# BPW34.net
KiCad netlist of a schematic drawn in EAGLE
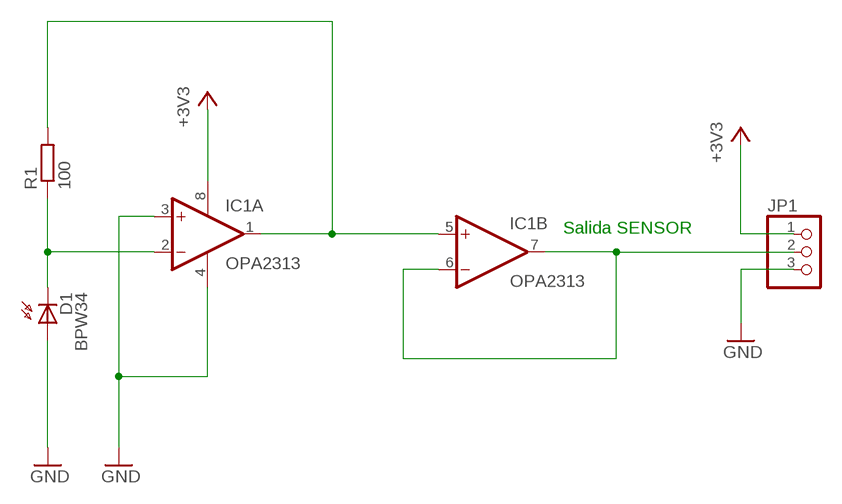
[diagram p0: schematic, sheet 1]

(export (version "E")
  (design (tool "Eeschema 10.0.6"))
  (components
    (comp (ref "D1")
      (value "BPW34")
      (footprint "eagle-import:BPW32")
      (libsource (lib "eagle-import") (part "BPW32"))
    )
    (comp (ref "IC1")
      (value "OPA2313")
      (footprint "eagle-import:SO08")
      (libsource (lib "eagle-import") (part "TL082D"))
    )
    (comp (ref "JP1")
      (value "PINHD-1X3")
      (footprint "eagle-import:1X03")
      (libsource (lib "eagle-import") (part "PINHD-1X3"))
    )
    (comp (ref "R1")
      (value "100")
      (footprint "eagle-import:0207_10")
      (libsource (lib "eagle-import") (part "R-EU_0207/10"))
    )
  )
  (nets
    (net (code "1") (name "+3V3") (class "Default")
      (node (ref "IC1") (pin "8") (pinfunction "V+_8") (pintype "power_in"))
      (node (ref "JP1") (pin "1") (pinfunction "1_1") (pintype "passive"))
    )
    (net (code "2") (name "GND") (class "Default")
      (node (ref "D1") (pin "A") (pinfunction "A_A") (pintype "passive"))
      (node (ref "IC1") (pin "3") (pinfunction "+IN_3") (pintype "input"))
      (node (ref "IC1") (pin "4") (pinfunction "V-_4") (pintype "power_in"))
      (node (ref "JP1") (pin "3") (pinfunction "3_3") (pintype "passive"))
    )
    (net (code "3") (name "Net-(D1-C)") (class "Default")
      (node (ref "D1") (pin "K") (pinfunction "C_K") (pintype "passive"))
      (node (ref "IC1") (pin "2") (pinfunction "-IN_2") (pintype "input"))
      (node (ref "R1") (pin "1") (pinfunction "1_1") (pintype "passive"))
    )
    (net (code "4") (name "Net-(IC1A-OUT)") (class "Default")
      (node (ref "IC1") (pin "1") (pinfunction "OUT_1") (pintype "output"))
      (node (ref "IC1") (pin "5") (pinfunction "+IN_5") (pintype "input"))
      (node (ref "R1") (pin "2") (pinfunction "2_2") (pintype "passive"))
    )
    (net (code "5") (name "Net-(IC1B--IN)") (class "Default")
      (node (ref "IC1") (pin "6") (pinfunction "-IN_6") (pintype "input"))
      (node (ref "IC1") (pin "7") (pinfunction "OUT_7") (pintype "output"))
      (node (ref "JP1") (pin "2") (pinfunction "2_2") (pintype "passive"))
    )
  )
)
